# ProPrj__-.net
KiCad netlist of a schematic drawn in EasyEDA Pro
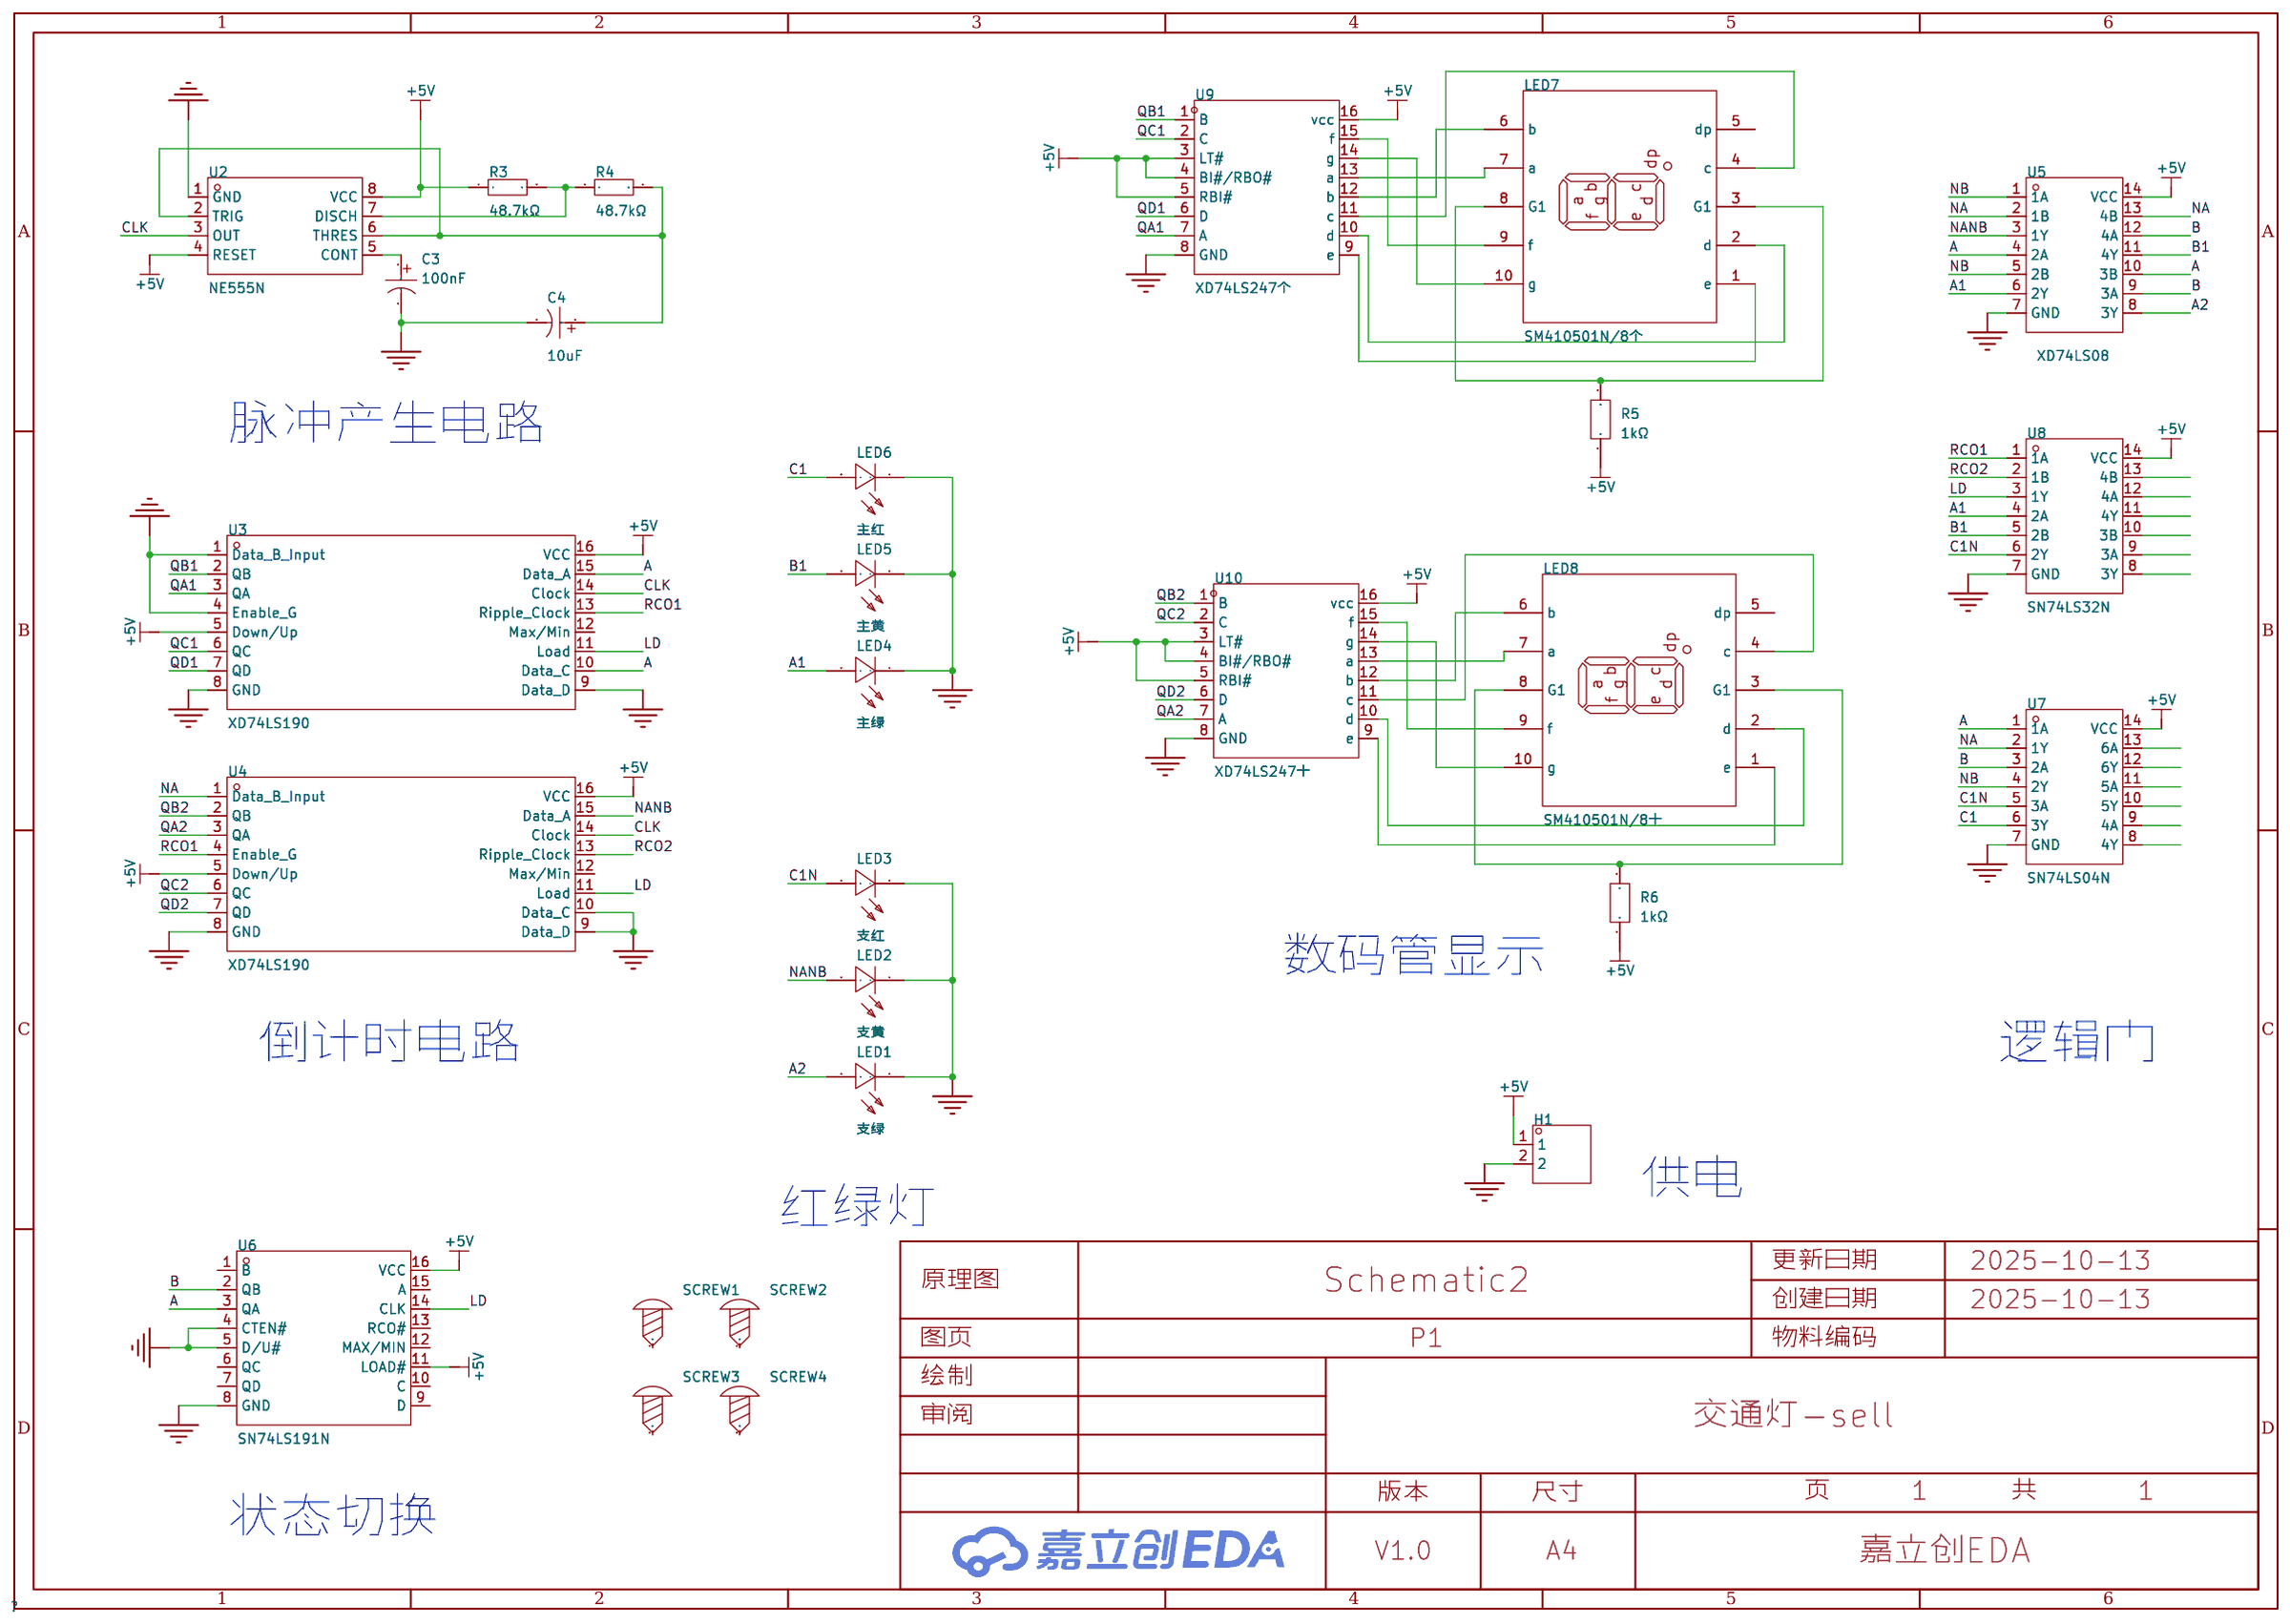
[diagram p0: schematic sheet]

(export (version "E")
  (design (tool "Eeschema 10.0.6"))
  (components
    (comp (ref "C3")
      (value "100nF")
      (footprint "easyedapro:CAP-TH_BD4.0-P1.50-D0.8-FD")
      (description "容值:100nF;精度:±20%;额定电压:50V;纹波电流:1A@100kHz;等效串联电阻:-;")
      (fields
        (field (name "Manufacturer Part") "KS104M050C07RR0VH2FP0")
        (field (name "Manufacturer") "CX(承兴)")
      )
      (libsource (lib "easyedapro") (part "0.1uF 50V 4*7"))
    )
    (comp (ref "C4")
      (value "10uF")
      (footprint "easyedapro:CAP-TH_BD5.0-P2.00-D0.8-FD")
      (description "容值:10uF;精度:±20%;额定电压:50V;")
      (fields (field (name "Manufacturer Part") "ERS1HM100D11OT") (field (name "Manufacturer") "AISHI(艾华集团)"))
      (libsource (lib "easyedapro") (part "ERS1HM100D11OT"))
    )
    (comp (ref "H1")
      (value "~")
      (footprint "easyedapro:HDR-TH_2P-P2.54-V-M-1")
      (libsource (lib "easyedapro") (part "210S-1*2P L=11.6MMGold-plated black"))
    )
    (comp (ref "LED1")
      (value "支绿")
      (footprint "easyedapro:LED-TH_BD3.9-P2.54-RD")
      (fields (field (name "Manufacturer") "EVERLIGHT(亿光)"))
      (libsource (lib "easyedapro") (part "204-10SUGD/S400-A4-L"))
    )
    (comp (ref "LED2")
      (value "支黄")
      (footprint "easyedapro:LED-TH_BD3.9-P2.54-RD")
      (fields (field (name "Manufacturer") "EVERLIGHT(亿光)"))
      (libsource (lib "easyedapro") (part "204-10SUGD/S400-A4-L"))
    )
    (comp (ref "LED3")
      (value "支红")
      (footprint "easyedapro:LED-TH_BD3.9-P2.54-RD")
      (fields (field (name "Manufacturer") "EVERLIGHT(亿光)"))
      (libsource (lib "easyedapro") (part "204-10SUGD/S400-A4-L"))
    )
    (comp (ref "LED4")
      (value "主绿")
      (footprint "easyedapro:LED-TH_BD3.9-P2.54-RD")
      (fields (field (name "Manufacturer") "EVERLIGHT(亿光)"))
      (libsource (lib "easyedapro") (part "204-10SUGD/S400-A4-L"))
    )
    (comp (ref "LED5")
      (value "主黄")
      (footprint "easyedapro:LED-TH_BD3.9-P2.54-RD")
      (fields (field (name "Manufacturer") "EVERLIGHT(亿光)"))
      (libsource (lib "easyedapro") (part "204-10SUGD/S400-A4-L"))
    )
    (comp (ref "LED6")
      (value "主红")
      (footprint "easyedapro:LED-TH_BD3.9-P2.54-RD")
      (fields (field (name "Manufacturer") "EVERLIGHT(亿光)"))
      (libsource (lib "easyedapro") (part "204-10SUGD/S400-A4-L"))
    )
    (comp (ref "LED7")
      (value "SM410501N/8个")
      (footprint "easyedapro:LED-SEG-TH_10P-L12.7-W19.0-P2.54-S15.24-BL")
      (description "数码管位数:1位;发光颜色:红色;LED极性:共阳极;数字/字母大小(英寸):0.5;")
      (fields (field (name "Manufacturer") "ARKLED(方舟)"))
      (libsource (lib "easyedapro") (part "SM410501N/8"))
    )
    (comp (ref "LED8")
      (value "SM410501N/8十")
      (footprint "easyedapro:LED-SEG-TH_10P-L12.7-W19.0-P2.54-S15.24-BL")
      (description "数码管位数:1位;发光颜色:红色;LED极性:共阳极;数字/字母大小(英寸):0.5;")
      (fields (field (name "Manufacturer") "ARKLED(方舟)"))
      (libsource (lib "easyedapro") (part "SM410501N/8"))
    )
    (comp (ref "R3")
      (value "48.7kΩ")
      (footprint "easyedapro:RES-TH_BD2.4-L6.3-P10.30-D0.6")
      (description "电阻类型:金属膜电阻;阻值:48.7kΩ;精度:±1%;功率:250mW;温度系数:±100ppm/°C;")
      (fields (field (name "Manufacturer Part") "MFR-25FBF52-48K7") (field (name "Manufacturer") "YAGEO(国巨)"))
      (libsource (lib "easyedapro") (part "MFR-25FBF52-48K7"))
    )
    (comp (ref "R4")
      (value "48.7kΩ")
      (footprint "easyedapro:RES-TH_BD2.4-L6.3-P10.30-D0.6")
      (description "电阻类型:金属膜电阻;阻值:48.7kΩ;精度:±1%;功率:250mW;温度系数:±100ppm/°C;")
      (fields (field (name "Manufacturer Part") "MFR-25FBF52-48K7") (field (name "Manufacturer") "YAGEO(国巨)"))
      (libsource (lib "easyedapro") (part "MFR-25FBF52-48K7"))
    )
    (comp (ref "R5")
      (value "1kΩ")
      (footprint "easyedapro:RES-TH_BD2.3-L6.5-P10.50-D0.5")
      (description "电阻类型:金属膜电阻;阻值:1kΩ;精度:±1%;功率:250mW;温度系数:±200ppm/°C;")
      (fields (field (name "Manufacturer Part") "MF1/4W-1KΩ±1%T52") (field (name "Manufacturer") "华星机电"))
      (libsource (lib "easyedapro") (part "MF1/4W-1KΩ±1%T52"))
    )
    (comp (ref "R6")
      (value "1kΩ")
      (footprint "easyedapro:RES-TH_BD2.3-L6.5-P10.50-D0.5")
      (description "电阻类型:金属膜电阻;阻值:1kΩ;精度:±1%;功率:250mW;温度系数:±200ppm/°C;")
      (fields (field (name "Manufacturer Part") "MF1/4W-1KΩ±1%T52") (field (name "Manufacturer") "华星机电"))
      (libsource (lib "easyedapro") (part "MF1/4W-1KΩ±1%T52"))
    )
    (comp (ref "SCREW1")
      (value "~")
      (footprint "easyedapro:M3螺丝")
      (libsource (lib "easyedapro") (part "螺丝孔"))
    )
    (comp (ref "SCREW2")
      (value "~")
      (footprint "easyedapro:M3螺丝")
      (libsource (lib "easyedapro") (part "螺丝孔"))
    )
    (comp (ref "SCREW3")
      (value "~")
      (footprint "easyedapro:M3螺丝")
      (libsource (lib "easyedapro") (part "螺丝孔"))
    )
    (comp (ref "SCREW4")
      (value "~")
      (footprint "easyedapro:M3螺丝")
      (libsource (lib "easyedapro") (part "螺丝孔"))
    )
    (comp (ref "U2")
      (value "NE555N")
      (footprint "easyedapro:DIP-8_L9.8-W6.6-P2.54-LS7.6-BL")
      (fields (field (name "Manufacturer") "HGSEMI(华冠)"))
      (libsource (lib "easyedapro") (part "NE555N"))
    )
    (comp (ref "U3")
      (value "XD74LS190")
      (footprint "easyedapro:DIP-16_L20.0-W6.4-P2.54-LS7.6-BL")
      (fields (field (name "Manufacturer") "XINLUDA(信路达)"))
      (libsource (lib "easyedapro") (part "XD74LS190"))
    )
    (comp (ref "U4")
      (value "XD74LS190")
      (footprint "easyedapro:DIP-16_L20.0-W6.4-P2.54-LS7.6-BL")
      (fields (field (name "Manufacturer") "XINLUDA(信路达)"))
      (libsource (lib "easyedapro") (part "XD74LS190"))
    )
    (comp (ref "U5")
      (value "XD74LS08")
      (footprint "easyedapro:DIP-14_L19.4-W6.4-P2.54-LS7.6-BL")
      (description "逻辑类型:-;")
      (fields (field (name "Manufacturer") "XINLUDA(信路达)"))
      (libsource (lib "easyedapro") (part "XD74LS08"))
    )
    (comp (ref "U6")
      (value "SN74LS191N")
      (footprint "easyedapro:PDIP-16_L19.3-W6.4-P2.54-LS7.94-BL")
      (description "工作电压:4.75V~5.25V;元件数:1;触发沿:上升沿;计数速率:25MHz;")
      (fields (field (name "Manufacturer") "TI(德州仪器)"))
      (libsource (lib "easyedapro") (part "SN74LS191N"))
    )
    (comp (ref "U7")
      (value "SN74LS04N")
      (footprint "easyedapro:DIP-14_L19.1-W6.4-P2.54-LS7.6-BL")
      (description "电源电压:2V~6V;供电电流(最大值):2uA;电路数:6;最大传播延迟(tpd):14ns@6V;")
      (fields (field (name "Manufacturer") "LX(灵星芯微)"))
      (libsource (lib "easyedapro") (part "sn74ls04n(lx)"))
    )
    (comp (ref "U8")
      (value "SN74LS32N")
      (footprint "easyedapro:DIP-14_L19.1-W6.4-P2.54-LS7.6-BL")
      (fields (field (name "Manufacturer") "LX(灵星芯微)"))
      (libsource (lib "easyedapro") (part "sn74ls32n_c22466295"))
    )
    (comp (ref "U9")
      (value "XD74LS247个")
      (footprint "easyedapro:DIP-16_L19.3-W6.4-P2.54-LS7.6-BL")
      (description "BCD 到 7 段解码器/驱动器")
      (fields (field (name "Manufacturer") "XINLUDA(信路达)"))
      (libsource (lib "easyedapro") (part "XD74LS247"))
    )
    (comp (ref "U10")
      (value "XD74LS247十")
      (footprint "easyedapro:DIP-16_L19.3-W6.4-P2.54-LS7.6-BL")
      (description "BCD 到 7 段解码器/驱动器")
      (fields (field (name "Manufacturer") "XINLUDA(信路达)"))
      (libsource (lib "easyedapro") (part "XD74LS247"))
    )
  )
  (nets
    (net (code "1") (name "+5V") (class "Default")
      (node (ref "H1") (pin "1") (pinfunction "1_1") (pintype "unspecified"))
      (node (ref "R3") (pin "1") (pinfunction "1_1") (pintype "unspecified"))
      (node (ref "R5") (pin "1") (pinfunction "1_1") (pintype "unspecified"))
      (node (ref "R6") (pin "1") (pinfunction "1_1") (pintype "unspecified"))
      (node (ref "U10") (pin "16") (pinfunction "vcc_16") (pintype "unspecified"))
      (node (ref "U10") (pin "3") (pinfunction "LT#_3") (pintype "unspecified"))
      (node (ref "U10") (pin "4") (pinfunction "BI#/RBO#_4") (pintype "unspecified"))
      (node (ref "U10") (pin "5") (pinfunction "RBI#_5") (pintype "unspecified"))
      (node (ref "U2") (pin "4") (pinfunction "RESET_4") (pintype "unspecified"))
      (node (ref "U2") (pin "8") (pinfunction "VCC_8") (pintype "unspecified"))
      (node (ref "U3") (pin "16") (pinfunction "VCC_16") (pintype "unspecified"))
      (node (ref "U3") (pin "5") (pinfunction "Down/Up_5") (pintype "unspecified"))
      (node (ref "U4") (pin "16") (pinfunction "VCC_16") (pintype "unspecified"))
      (node (ref "U4") (pin "5") (pinfunction "Down/Up_5") (pintype "unspecified"))
      (node (ref "U5") (pin "14") (pinfunction "VCC_14") (pintype "input"))
      (node (ref "U6") (pin "11") (pinfunction "LOAD#_11") (pintype "unspecified"))
      (node (ref "U6") (pin "16") (pinfunction "VCC_16") (pintype "unspecified"))
      (node (ref "U7") (pin "14") (pinfunction "VCC_14") (pintype "unspecified"))
      (node (ref "U8") (pin "14") (pinfunction "VCC_14") (pintype "unspecified"))
      (node (ref "U9") (pin "16") (pinfunction "vcc_16") (pintype "unspecified"))
      (node (ref "U9") (pin "3") (pinfunction "LT#_3") (pintype "unspecified"))
      (node (ref "U9") (pin "4") (pinfunction "BI#/RBO#_4") (pintype "unspecified"))
      (node (ref "U9") (pin "5") (pinfunction "RBI#_5") (pintype "unspecified"))
    )
    (net (code "2") (name "/A") (class "Default")
      (node (ref "U3") (pin "10") (pinfunction "Data_C_10") (pintype "unspecified"))
      (node (ref "U3") (pin "15") (pinfunction "Data_A_15") (pintype "unspecified"))
      (node (ref "U5") (pin "10") (pinfunction "3B_10") (pintype "input"))
      (node (ref "U5") (pin "4") (pinfunction "2A_4") (pintype "input"))
      (node (ref "U6") (pin "3") (pinfunction "QA_3") (pintype "unspecified"))
      (node (ref "U7") (pin "1") (pinfunction "1A_1") (pintype "unspecified"))
    )
    (net (code "3") (name "/A1") (class "Default")
      (node (ref "LED4") (pin "2") (pinfunction "+_2") (pintype "input"))
      (node (ref "U5") (pin "6") (pinfunction "2Y_6") (pintype "input"))
      (node (ref "U8") (pin "4") (pinfunction "2A_4") (pintype "unspecified"))
    )
    (net (code "4") (name "/A2") (class "Default")
      (node (ref "LED1") (pin "2") (pinfunction "+_2") (pintype "input"))
      (node (ref "U5") (pin "8") (pinfunction "3Y_8") (pintype "input"))
    )
    (net (code "5") (name "/B") (class "Default")
      (node (ref "U5") (pin "12") (pinfunction "4A_12") (pintype "input"))
      (node (ref "U5") (pin "9") (pinfunction "3A_9") (pintype "input"))
      (node (ref "U6") (pin "2") (pinfunction "QB_2") (pintype "unspecified"))
      (node (ref "U7") (pin "3") (pinfunction "2A_3") (pintype "unspecified"))
    )
    (net (code "6") (name "/B1") (class "Default")
      (node (ref "LED5") (pin "2") (pinfunction "+_2") (pintype "input"))
      (node (ref "U5") (pin "11") (pinfunction "4Y_11") (pintype "input"))
      (node (ref "U8") (pin "5") (pinfunction "2B_5") (pintype "unspecified"))
    )
    (net (code "7") (name "/C1") (class "Default")
      (node (ref "LED6") (pin "2") (pinfunction "+_2") (pintype "input"))
      (node (ref "U7") (pin "6") (pinfunction "3Y_6") (pintype "unspecified"))
    )
    (net (code "8") (name "/C1N") (class "Default")
      (node (ref "LED3") (pin "2") (pinfunction "+_2") (pintype "input"))
      (node (ref "U7") (pin "5") (pinfunction "3A_5") (pintype "unspecified"))
      (node (ref "U8") (pin "6") (pinfunction "2Y_6") (pintype "unspecified"))
    )
    (net (code "9") (name "/CLK") (class "Default")
      (node (ref "U2") (pin "3") (pinfunction "OUT_3") (pintype "unspecified"))
      (node (ref "U3") (pin "14") (pinfunction "Clock_14") (pintype "unspecified"))
      (node (ref "U4") (pin "14") (pinfunction "Clock_14") (pintype "unspecified"))
    )
    (net (code "10") (name "/LD") (class "Default")
      (node (ref "U3") (pin "11") (pinfunction "Load_11") (pintype "unspecified"))
      (node (ref "U4") (pin "11") (pinfunction "Load_11") (pintype "unspecified"))
      (node (ref "U6") (pin "14") (pinfunction "CLK_14") (pintype "unspecified"))
      (node (ref "U8") (pin "3") (pinfunction "1Y_3") (pintype "unspecified"))
    )
    (net (code "11") (name "/NA") (class "Default")
      (node (ref "U4") (pin "1") (pinfunction "Data_B_Input_1") (pintype "unspecified"))
      (node (ref "U5") (pin "13") (pinfunction "4B_13") (pintype "input"))
      (node (ref "U5") (pin "2") (pinfunction "1B_2") (pintype "input"))
      (node (ref "U7") (pin "2") (pinfunction "1Y_2") (pintype "unspecified"))
    )
    (net (code "12") (name "/NANB") (class "Default")
      (node (ref "LED2") (pin "2") (pinfunction "+_2") (pintype "input"))
      (node (ref "U4") (pin "15") (pinfunction "Data_A_15") (pintype "unspecified"))
      (node (ref "U5") (pin "3") (pinfunction "1Y_3") (pintype "input"))
    )
    (net (code "13") (name "/NB") (class "Default")
      (node (ref "U5") (pin "1") (pinfunction "1A_1") (pintype "input"))
      (node (ref "U5") (pin "5") (pinfunction "2B_5") (pintype "input"))
      (node (ref "U7") (pin "4") (pinfunction "2Y_4") (pintype "unspecified"))
    )
    (net (code "14") (name "/QA1") (class "Default")
      (node (ref "U3") (pin "3") (pinfunction "QA_3") (pintype "unspecified"))
      (node (ref "U9") (pin "7") (pinfunction "A_7") (pintype "unspecified"))
    )
    (net (code "15") (name "/QA2") (class "Default")
      (node (ref "U10") (pin "7") (pinfunction "A_7") (pintype "unspecified"))
      (node (ref "U4") (pin "3") (pinfunction "QA_3") (pintype "unspecified"))
    )
    (net (code "16") (name "/QB1") (class "Default")
      (node (ref "U3") (pin "2") (pinfunction "QB_2") (pintype "unspecified"))
      (node (ref "U9") (pin "1") (pinfunction "B_1") (pintype "unspecified"))
    )
    (net (code "17") (name "/QB2") (class "Default")
      (node (ref "U10") (pin "1") (pinfunction "B_1") (pintype "unspecified"))
      (node (ref "U4") (pin "2") (pinfunction "QB_2") (pintype "unspecified"))
    )
    (net (code "18") (name "/QC1") (class "Default")
      (node (ref "U3") (pin "6") (pinfunction "QC_6") (pintype "unspecified"))
      (node (ref "U9") (pin "2") (pinfunction "C_2") (pintype "unspecified"))
    )
    (net (code "19") (name "/QC2") (class "Default")
      (node (ref "U10") (pin "2") (pinfunction "C_2") (pintype "unspecified"))
      (node (ref "U4") (pin "6") (pinfunction "QC_6") (pintype "unspecified"))
    )
    (net (code "20") (name "/QD1") (class "Default")
      (node (ref "U3") (pin "7") (pinfunction "QD_7") (pintype "unspecified"))
      (node (ref "U9") (pin "6") (pinfunction "D_6") (pintype "unspecified"))
    )
    (net (code "21") (name "/QD2") (class "Default")
      (node (ref "U10") (pin "6") (pinfunction "D_6") (pintype "unspecified"))
      (node (ref "U4") (pin "7") (pinfunction "QD_7") (pintype "unspecified"))
    )
    (net (code "22") (name "/RCO1") (class "Default")
      (node (ref "U3") (pin "13") (pinfunction "Ripple_Clock_13") (pintype "unspecified"))
      (node (ref "U4") (pin "4") (pinfunction "Enable_G_4") (pintype "unspecified"))
      (node (ref "U8") (pin "1") (pinfunction "1A_1") (pintype "unspecified"))
    )
    (net (code "23") (name "/RCO2") (class "Default")
      (node (ref "U4") (pin "13") (pinfunction "Ripple_Clock_13") (pintype "unspecified"))
      (node (ref "U8") (pin "2") (pinfunction "1B_2") (pintype "unspecified"))
    )
    (net (code "24") (name "GND") (class "Default")
      (node (ref "C3") (pin "2") (pinfunction "2_2") (pintype "input"))
      (node (ref "C4") (pin "2") (pinfunction "2_2") (pintype "input"))
      (node (ref "H1") (pin "2") (pinfunction "2_2") (pintype "unspecified"))
      (node (ref "LED1") (pin "1") (pinfunction "-_1") (pintype "input"))
      (node (ref "LED2") (pin "1") (pinfunction "-_1") (pintype "input"))
      (node (ref "LED3") (pin "1") (pinfunction "-_1") (pintype "input"))
      (node (ref "LED4") (pin "1") (pinfunction "-_1") (pintype "input"))
      (node (ref "LED5") (pin "1") (pinfunction "-_1") (pintype "input"))
      (node (ref "LED6") (pin "1") (pinfunction "-_1") (pintype "input"))
      (node (ref "U10") (pin "8") (pinfunction "GND_8") (pintype "unspecified"))
      (node (ref "U2") (pin "1") (pinfunction "GND_1") (pintype "unspecified"))
      (node (ref "U3") (pin "1") (pinfunction "Data_B_Input_1") (pintype "unspecified"))
      (node (ref "U3") (pin "4") (pinfunction "Enable_G_4") (pintype "unspecified"))
      (node (ref "U3") (pin "8") (pinfunction "GND_8") (pintype "unspecified"))
      (node (ref "U3") (pin "9") (pinfunction "Data_D_9") (pintype "unspecified"))
      (node (ref "U4") (pin "10") (pinfunction "Data_C_10") (pintype "unspecified"))
      (node (ref "U4") (pin "8") (pinfunction "GND_8") (pintype "unspecified"))
      (node (ref "U4") (pin "9") (pinfunction "Data_D_9") (pintype "unspecified"))
      (node (ref "U5") (pin "7") (pinfunction "GND_7") (pintype "input"))
      (node (ref "U6") (pin "4") (pinfunction "CTEN#_4") (pintype "unspecified"))
      (node (ref "U6") (pin "5") (pinfunction "D/U#_5") (pintype "unspecified"))
      (node (ref "U6") (pin "8") (pinfunction "GND_8") (pintype "unspecified"))
      (node (ref "U7") (pin "7") (pinfunction "GND_7") (pintype "unspecified"))
      (node (ref "U8") (pin "7") (pinfunction "GND_7") (pintype "unspecified"))
      (node (ref "U9") (pin "8") (pinfunction "GND_8") (pintype "unspecified"))
    )
    (net (code "25") (name "Net-(LED7-G1-Pad3)") (class "Default")
      (node (ref "LED7") (pin "3") (pinfunction "G1_3") (pintype "input"))
      (node (ref "LED7") (pin "8") (pinfunction "G1_8") (pintype "input"))
      (node (ref "R5") (pin "2") (pinfunction "2_2") (pintype "unspecified"))
    )
    (net (code "26") (name "Net-(LED7-a)") (class "Default")
      (node (ref "LED7") (pin "7") (pinfunction "a_7") (pintype "input"))
      (node (ref "U9") (pin "13") (pinfunction "a_13") (pintype "unspecified"))
    )
    (net (code "27") (name "Net-(LED7-b)") (class "Default")
      (node (ref "LED7") (pin "6") (pinfunction "b_6") (pintype "input"))
      (node (ref "U9") (pin "12") (pinfunction "b_12") (pintype "unspecified"))
    )
    (net (code "28") (name "Net-(LED7-c)") (class "Default")
      (node (ref "LED7") (pin "4") (pinfunction "c_4") (pintype "input"))
      (node (ref "U9") (pin "11") (pinfunction "c_11") (pintype "unspecified"))
    )
    (net (code "29") (name "Net-(LED7-d)") (class "Default")
      (node (ref "LED7") (pin "2") (pinfunction "d_2") (pintype "input"))
      (node (ref "U9") (pin "10") (pinfunction "d_10") (pintype "unspecified"))
    )
    (net (code "30") (name "Net-(LED7-e)") (class "Default")
      (node (ref "LED7") (pin "1") (pinfunction "e_1") (pintype "input"))
      (node (ref "U9") (pin "9") (pinfunction "e_9") (pintype "unspecified"))
    )
    (net (code "31") (name "Net-(LED7-f)") (class "Default")
      (node (ref "LED7") (pin "9") (pinfunction "f_9") (pintype "input"))
      (node (ref "U9") (pin "15") (pinfunction "f_15") (pintype "unspecified"))
    )
    (net (code "32") (name "Net-(LED7-g)") (class "Default")
      (node (ref "LED7") (pin "10") (pinfunction "g_10") (pintype "input"))
      (node (ref "U9") (pin "14") (pinfunction "g_14") (pintype "unspecified"))
    )
    (net (code "33") (name "Net-(LED8-G1-Pad3)") (class "Default")
      (node (ref "LED8") (pin "3") (pinfunction "G1_3") (pintype "input"))
      (node (ref "LED8") (pin "8") (pinfunction "G1_8") (pintype "input"))
      (node (ref "R6") (pin "2") (pinfunction "2_2") (pintype "unspecified"))
    )
    (net (code "34") (name "Net-(LED8-a)") (class "Default")
      (node (ref "LED8") (pin "7") (pinfunction "a_7") (pintype "input"))
      (node (ref "U10") (pin "13") (pinfunction "a_13") (pintype "unspecified"))
    )
    (net (code "35") (name "Net-(LED8-b)") (class "Default")
      (node (ref "LED8") (pin "6") (pinfunction "b_6") (pintype "input"))
      (node (ref "U10") (pin "12") (pinfunction "b_12") (pintype "unspecified"))
    )
    (net (code "36") (name "Net-(LED8-c)") (class "Default")
      (node (ref "LED8") (pin "4") (pinfunction "c_4") (pintype "input"))
      (node (ref "U10") (pin "11") (pinfunction "c_11") (pintype "unspecified"))
    )
    (net (code "37") (name "Net-(LED8-d)") (class "Default")
      (node (ref "LED8") (pin "2") (pinfunction "d_2") (pintype "input"))
      (node (ref "U10") (pin "10") (pinfunction "d_10") (pintype "unspecified"))
    )
    (net (code "38") (name "Net-(LED8-e)") (class "Default")
      (node (ref "LED8") (pin "1") (pinfunction "e_1") (pintype "input"))
      (node (ref "U10") (pin "9") (pinfunction "e_9") (pintype "unspecified"))
    )
    (net (code "39") (name "Net-(LED8-f)") (class "Default")
      (node (ref "LED8") (pin "9") (pinfunction "f_9") (pintype "input"))
      (node (ref "U10") (pin "15") (pinfunction "f_15") (pintype "unspecified"))
    )
    (net (code "40") (name "Net-(LED8-g)") (class "Default")
      (node (ref "LED8") (pin "10") (pinfunction "g_10") (pintype "input"))
      (node (ref "U10") (pin "14") (pinfunction "g_14") (pintype "unspecified"))
    )
    (net (code "41") (name "Net-(U2-CONT)") (class "Default")
      (node (ref "C3") (pin "1") (pinfunction "1_1") (pintype "input"))
      (node (ref "U2") (pin "5") (pinfunction "CONT_5") (pintype "unspecified"))
    )
    (net (code "42") (name "Net-(U2-DISCH)") (class "Default")
      (node (ref "R3") (pin "2") (pinfunction "2_2") (pintype "unspecified"))
      (node (ref "R4") (pin "1") (pinfunction "1_1") (pintype "unspecified"))
      (node (ref "U2") (pin "7") (pinfunction "DISCH_7") (pintype "unspecified"))
    )
    (net (code "43") (name "Net-(U2-THRES)") (class "Default")
      (node (ref "C4") (pin "1") (pinfunction "1_1") (pintype "input"))
      (node (ref "R4") (pin "2") (pinfunction "2_2") (pintype "unspecified"))
      (node (ref "U2") (pin "2") (pinfunction "TRIG_2") (pintype "unspecified"))
      (node (ref "U2") (pin "6") (pinfunction "THRES_6") (pintype "unspecified"))
    )
    (net (code "44") (name "unconnected-(LED7-dp-Pad5)") (class "Default")
      (node (ref "LED7") (pin "5") (pinfunction "dp_5") (pintype "input"))
    )
    (net (code "45") (name "unconnected-(LED8-dp-Pad5)") (class "Default")
      (node (ref "LED8") (pin "5") (pinfunction "dp_5") (pintype "input"))
    )
    (net (code "46") (name "unconnected-(SCREW1-Pad1)") (class "Default")
      (node (ref "SCREW1") (pin "1") (pinfunction "1_1") (pintype "input"))
    )
    (net (code "47") (name "unconnected-(SCREW2-Pad1)") (class "Default")
      (node (ref "SCREW2") (pin "1") (pinfunction "1_1") (pintype "input"))
    )
    (net (code "48") (name "unconnected-(SCREW3-Pad1)") (class "Default")
      (node (ref "SCREW3") (pin "1") (pinfunction "1_1") (pintype "input"))
    )
    (net (code "49") (name "unconnected-(SCREW4-Pad1)") (class "Default")
      (node (ref "SCREW4") (pin "1") (pinfunction "1_1") (pintype "input"))
    )
    (net (code "50") (name "unconnected-(U3-Max{slash}Min-Pad12)") (class "Default")
      (node (ref "U3") (pin "12") (pinfunction "Max/Min_12") (pintype "unspecified"))
    )
    (net (code "51") (name "unconnected-(U4-Max{slash}Min-Pad12)") (class "Default")
      (node (ref "U4") (pin "12") (pinfunction "Max/Min_12") (pintype "unspecified"))
    )
    (net (code "52") (name "unconnected-(U6-A-Pad15)") (class "Default")
      (node (ref "U6") (pin "15") (pinfunction "A_15") (pintype "unspecified"))
    )
    (net (code "53") (name "unconnected-(U6-B-Pad1)") (class "Default")
      (node (ref "U6") (pin "1") (pinfunction "B_1") (pintype "unspecified"))
    )
    (net (code "54") (name "unconnected-(U6-C-Pad10)") (class "Default")
      (node (ref "U6") (pin "10") (pinfunction "C_10") (pintype "unspecified"))
    )
    (net (code "55") (name "unconnected-(U6-D-Pad9)") (class "Default")
      (node (ref "U6") (pin "9") (pinfunction "D_9") (pintype "unspecified"))
    )
    (net (code "56") (name "unconnected-(U6-MAX{slash}MIN-Pad12)") (class "Default")
      (node (ref "U6") (pin "12") (pinfunction "MAX/MIN_12") (pintype "unspecified"))
    )
    (net (code "57") (name "unconnected-(U6-QC-Pad6)") (class "Default")
      (node (ref "U6") (pin "6") (pinfunction "QC_6") (pintype "unspecified"))
    )
    (net (code "58") (name "unconnected-(U6-QD-Pad7)") (class "Default")
      (node (ref "U6") (pin "7") (pinfunction "QD_7") (pintype "unspecified"))
    )
    (net (code "59") (name "unconnected-(U6-RCO#-Pad13)") (class "Default")
      (node (ref "U6") (pin "13") (pinfunction "RCO#_13") (pintype "unspecified"))
    )
    (net (code "60") (name "unconnected-(U7-4A-Pad9)") (class "Default")
      (node (ref "U7") (pin "9") (pinfunction "4A_9") (pintype "unspecified"))
    )
    (net (code "61") (name "unconnected-(U7-4Y-Pad8)") (class "Default")
      (node (ref "U7") (pin "8") (pinfunction "4Y_8") (pintype "unspecified"))
    )
    (net (code "62") (name "unconnected-(U7-5A-Pad11)") (class "Default")
      (node (ref "U7") (pin "11") (pinfunction "5A_11") (pintype "unspecified"))
    )
    (net (code "63") (name "unconnected-(U7-5Y-Pad10)") (class "Default")
      (node (ref "U7") (pin "10") (pinfunction "5Y_10") (pintype "unspecified"))
    )
    (net (code "64") (name "unconnected-(U7-6A-Pad13)") (class "Default")
      (node (ref "U7") (pin "13") (pinfunction "6A_13") (pintype "unspecified"))
    )
    (net (code "65") (name "unconnected-(U7-6Y-Pad12)") (class "Default")
      (node (ref "U7") (pin "12") (pinfunction "6Y_12") (pintype "unspecified"))
    )
    (net (code "66") (name "unconnected-(U8-3A-Pad9)") (class "Default")
      (node (ref "U8") (pin "9") (pinfunction "3A_9") (pintype "unspecified"))
    )
    (net (code "67") (name "unconnected-(U8-3B-Pad10)") (class "Default")
      (node (ref "U8") (pin "10") (pinfunction "3B_10") (pintype "unspecified"))
    )
    (net (code "68") (name "unconnected-(U8-3Y-Pad8)") (class "Default")
      (node (ref "U8") (pin "8") (pinfunction "3Y_8") (pintype "unspecified"))
    )
    (net (code "69") (name "unconnected-(U8-4A-Pad12)") (class "Default")
      (node (ref "U8") (pin "12") (pinfunction "4A_12") (pintype "unspecified"))
    )
    (net (code "70") (name "unconnected-(U8-4B-Pad13)") (class "Default")
      (node (ref "U8") (pin "13") (pinfunction "4B_13") (pintype "unspecified"))
    )
    (net (code "71") (name "unconnected-(U8-4Y-Pad11)") (class "Default")
      (node (ref "U8") (pin "11") (pinfunction "4Y_11") (pintype "unspecified"))
    )
  )
)
